# beginner.net
KiCad netlist of a schematic drawn in EAGLE
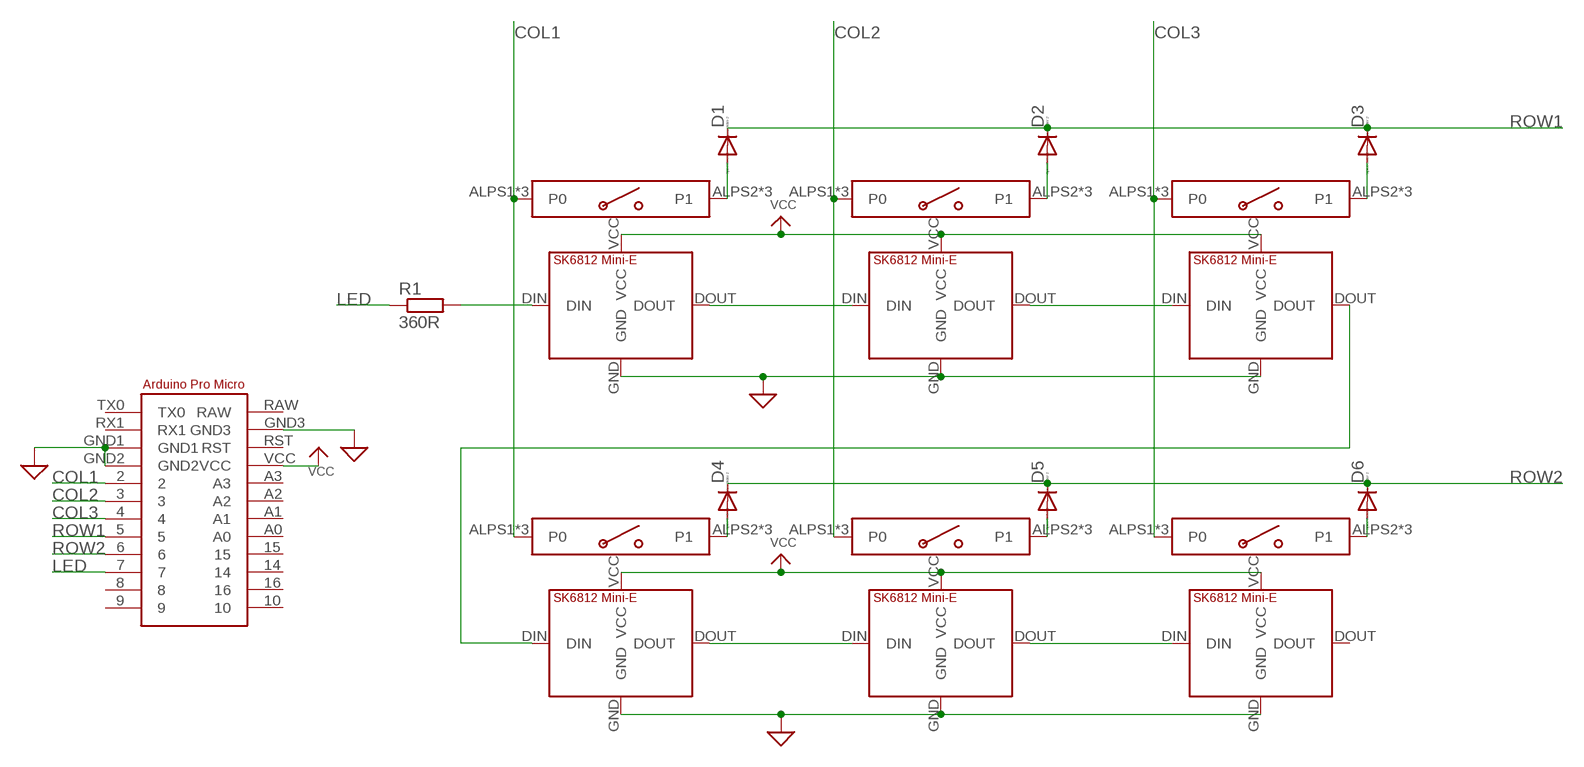
[diagram p0: schematic, sheet 1]

(export (version "E")
  (design (tool "Eeschema 10.0.6"))
  (components
    (comp (ref "D1")
      (value "1N41481N4148_THROUGH")
      (footprint "eagle-import:DIODE-1N4148")
      (libsource (lib "eagle-import") (part "1N41481N4148_THROUGH"))
    )
    (comp (ref "D2")
      (value "1N41481N4148_THROUGH")
      (footprint "eagle-import:DIODE-1N4148")
      (libsource (lib "eagle-import") (part "1N41481N4148_THROUGH"))
    )
    (comp (ref "D3")
      (value "1N41481N4148_THROUGH")
      (footprint "eagle-import:DIODE-1N4148")
      (libsource (lib "eagle-import") (part "1N41481N4148_THROUGH"))
    )
    (comp (ref "D4")
      (value "1N41481N4148_THROUGH")
      (footprint "eagle-import:DIODE-1N4148")
      (libsource (lib "eagle-import") (part "1N41481N4148_THROUGH"))
    )
    (comp (ref "D5")
      (value "1N41481N4148_THROUGH")
      (footprint "eagle-import:DIODE-1N4148")
      (libsource (lib "eagle-import") (part "1N41481N4148_THROUGH"))
    )
    (comp (ref "D6")
      (value "1N41481N4148_THROUGH")
      (footprint "eagle-import:DIODE-1N4148")
      (libsource (lib "eagle-import") (part "1N41481N4148_THROUGH"))
    )
    (comp (ref "R1")
      (value "360R")
      (footprint "eagle-import:THT-RESISTOR")
      (libsource (lib "eagle-import") (part "RESISTOR-THT"))
    )
    (comp (ref "U$1")
      (value "ARDUINO_PRO_MICRO")
      (footprint "eagle-import:ARDUINO_PRO_MICRO")
      (libsource (lib "eagle-import") (part "ARDUINO_PRO_MICRO"))
    )
    (comp (ref "U$2")
      (value "KEYSWITCH-SK6812")
      (footprint "eagle-import:UNIVERSAL_KEYSWITCH_SK6812MINIE")
      (libsource (lib "eagle-import") (part "KEYSWITCH-SK6812"))
    )
    (comp (ref "U$3")
      (value "KEYSWITCH-SK6812")
      (footprint "eagle-import:UNIVERSAL_KEYSWITCH_SK6812MINIE")
      (libsource (lib "eagle-import") (part "KEYSWITCH-SK6812"))
    )
    (comp (ref "U$4")
      (value "KEYSWITCH-SK6812")
      (footprint "eagle-import:UNIVERSAL_KEYSWITCH_SK6812MINIE")
      (libsource (lib "eagle-import") (part "KEYSWITCH-SK6812"))
    )
    (comp (ref "U$5")
      (value "KEYSWITCH-SK6812")
      (footprint "eagle-import:UNIVERSAL_KEYSWITCH_SK6812MINIE")
      (libsource (lib "eagle-import") (part "KEYSWITCH-SK6812"))
    )
    (comp (ref "U$6")
      (value "KEYSWITCH-SK6812")
      (footprint "eagle-import:UNIVERSAL_KEYSWITCH_SK6812MINIE")
      (libsource (lib "eagle-import") (part "KEYSWITCH-SK6812"))
    )
    (comp (ref "U$7")
      (value "KEYSWITCH-SK6812")
      (footprint "eagle-import:UNIVERSAL_KEYSWITCH_SK6812MINIE")
      (libsource (lib "eagle-import") (part "KEYSWITCH-SK6812"))
    )
  )
  (nets
    (net (code "1") (name "/COL1") (class "Default")
      (node (ref "U$1") (pin "2") (pinfunction "2_2") (pintype "bidirectional"))
      (node (ref "U$2") (pin "ALPS1") (pinfunction "P0_ALPS1") (pintype "bidirectional"))
      (node (ref "U$2") (pin "CHOC1") (pinfunction "P0_CHOC1") (pintype "bidirectional"))
      (node (ref "U$2") (pin "MX1") (pinfunction "P0_MX1") (pintype "bidirectional"))
      (node (ref "U$5") (pin "ALPS1") (pinfunction "P0_ALPS1") (pintype "bidirectional"))
      (node (ref "U$5") (pin "CHOC1") (pinfunction "P0_CHOC1") (pintype "bidirectional"))
      (node (ref "U$5") (pin "MX1") (pinfunction "P0_MX1") (pintype "bidirectional"))
    )
    (net (code "2") (name "/COL2") (class "Default")
      (node (ref "U$1") (pin "3") (pinfunction "3_3") (pintype "bidirectional"))
      (node (ref "U$3") (pin "ALPS1") (pinfunction "P0_ALPS1") (pintype "bidirectional"))
      (node (ref "U$3") (pin "CHOC1") (pinfunction "P0_CHOC1") (pintype "bidirectional"))
      (node (ref "U$3") (pin "MX1") (pinfunction "P0_MX1") (pintype "bidirectional"))
      (node (ref "U$6") (pin "ALPS1") (pinfunction "P0_ALPS1") (pintype "bidirectional"))
      (node (ref "U$6") (pin "CHOC1") (pinfunction "P0_CHOC1") (pintype "bidirectional"))
      (node (ref "U$6") (pin "MX1") (pinfunction "P0_MX1") (pintype "bidirectional"))
    )
    (net (code "3") (name "/COL3") (class "Default")
      (node (ref "U$1") (pin "4") (pinfunction "4_4") (pintype "bidirectional"))
      (node (ref "U$4") (pin "ALPS1") (pinfunction "P0_ALPS1") (pintype "bidirectional"))
      (node (ref "U$4") (pin "CHOC1") (pinfunction "P0_CHOC1") (pintype "bidirectional"))
      (node (ref "U$4") (pin "MX1") (pinfunction "P0_MX1") (pintype "bidirectional"))
      (node (ref "U$7") (pin "ALPS1") (pinfunction "P0_ALPS1") (pintype "bidirectional"))
      (node (ref "U$7") (pin "CHOC1") (pinfunction "P0_CHOC1") (pintype "bidirectional"))
      (node (ref "U$7") (pin "MX1") (pinfunction "P0_MX1") (pintype "bidirectional"))
    )
    (net (code "4") (name "/LED") (class "Default")
      (node (ref "R1") (pin "1") (pinfunction "1_1") (pintype "passive"))
      (node (ref "U$1") (pin "7") (pinfunction "7_7") (pintype "bidirectional"))
    )
    (net (code "5") (name "/ROW1") (class "Default")
      (node (ref "D1") (pin "C") (pinfunction "C_C") (pintype "passive"))
      (node (ref "D2") (pin "C") (pinfunction "C_C") (pintype "passive"))
      (node (ref "D3") (pin "C") (pinfunction "C_C") (pintype "passive"))
      (node (ref "U$1") (pin "5") (pinfunction "5_5") (pintype "bidirectional"))
    )
    (net (code "6") (name "/ROW2") (class "Default")
      (node (ref "D4") (pin "C") (pinfunction "C_C") (pintype "passive"))
      (node (ref "D5") (pin "C") (pinfunction "C_C") (pintype "passive"))
      (node (ref "D6") (pin "C") (pinfunction "C_C") (pintype "passive"))
      (node (ref "U$1") (pin "6") (pinfunction "6_6") (pintype "bidirectional"))
    )
    (net (code "7") (name "Net-(D1-PadA)") (class "Default")
      (node (ref "D1") (pin "A") (pinfunction "A_A") (pintype "passive"))
      (node (ref "U$2") (pin "ALPS2") (pinfunction "P1_ALPS2") (pintype "bidirectional"))
      (node (ref "U$2") (pin "CHOC2") (pinfunction "P1_CHOC2") (pintype "bidirectional"))
      (node (ref "U$2") (pin "MX2") (pinfunction "P1_MX2") (pintype "bidirectional"))
    )
    (net (code "8") (name "Net-(D2-PadA)") (class "Default")
      (node (ref "D2") (pin "A") (pinfunction "A_A") (pintype "passive"))
      (node (ref "U$3") (pin "ALPS2") (pinfunction "P1_ALPS2") (pintype "bidirectional"))
      (node (ref "U$3") (pin "CHOC2") (pinfunction "P1_CHOC2") (pintype "bidirectional"))
      (node (ref "U$3") (pin "MX2") (pinfunction "P1_MX2") (pintype "bidirectional"))
    )
    (net (code "9") (name "Net-(D3-PadA)") (class "Default")
      (node (ref "D3") (pin "A") (pinfunction "A_A") (pintype "passive"))
      (node (ref "U$4") (pin "ALPS2") (pinfunction "P1_ALPS2") (pintype "bidirectional"))
      (node (ref "U$4") (pin "CHOC2") (pinfunction "P1_CHOC2") (pintype "bidirectional"))
      (node (ref "U$4") (pin "MX2") (pinfunction "P1_MX2") (pintype "bidirectional"))
    )
    (net (code "10") (name "Net-(D4-PadA)") (class "Default")
      (node (ref "D4") (pin "A") (pinfunction "A_A") (pintype "passive"))
      (node (ref "U$5") (pin "ALPS2") (pinfunction "P1_ALPS2") (pintype "bidirectional"))
      (node (ref "U$5") (pin "CHOC2") (pinfunction "P1_CHOC2") (pintype "bidirectional"))
      (node (ref "U$5") (pin "MX2") (pinfunction "P1_MX2") (pintype "bidirectional"))
    )
    (net (code "11") (name "Net-(D5-PadA)") (class "Default")
      (node (ref "D5") (pin "A") (pinfunction "A_A") (pintype "passive"))
      (node (ref "U$6") (pin "ALPS2") (pinfunction "P1_ALPS2") (pintype "bidirectional"))
      (node (ref "U$6") (pin "CHOC2") (pinfunction "P1_CHOC2") (pintype "bidirectional"))
      (node (ref "U$6") (pin "MX2") (pinfunction "P1_MX2") (pintype "bidirectional"))
    )
    (net (code "12") (name "Net-(D6-PadA)") (class "Default")
      (node (ref "D6") (pin "A") (pinfunction "A_A") (pintype "passive"))
      (node (ref "U$7") (pin "ALPS2") (pinfunction "P1_ALPS2") (pintype "bidirectional"))
      (node (ref "U$7") (pin "CHOC2") (pinfunction "P1_CHOC2") (pintype "bidirectional"))
      (node (ref "U$7") (pin "MX2") (pinfunction "P1_MX2") (pintype "bidirectional"))
    )
    (net (code "13") (name "Net-(R1-Pad2)") (class "Default")
      (node (ref "R1") (pin "2") (pinfunction "2_2") (pintype "passive"))
      (node (ref "U$2") (pin "DIN") (pinfunction "DIN_DIN") (pintype "bidirectional"))
    )
    (net (code "14") (name "Net-(U$2-PadDOUT)") (class "Default")
      (node (ref "U$2") (pin "DOUT") (pinfunction "DOUT_DOUT") (pintype "bidirectional"))
      (node (ref "U$3") (pin "DIN") (pinfunction "DIN_DIN") (pintype "bidirectional"))
    )
    (net (code "15") (name "Net-(U$3-PadDOUT)") (class "Default")
      (node (ref "U$3") (pin "DOUT") (pinfunction "DOUT_DOUT") (pintype "bidirectional"))
      (node (ref "U$4") (pin "DIN") (pinfunction "DIN_DIN") (pintype "bidirectional"))
    )
    (net (code "16") (name "Net-(U$4-PadDOUT)") (class "Default")
      (node (ref "U$4") (pin "DOUT") (pinfunction "DOUT_DOUT") (pintype "bidirectional"))
      (node (ref "U$5") (pin "DIN") (pinfunction "DIN_DIN") (pintype "bidirectional"))
    )
    (net (code "17") (name "Net-(U$5-PadDOUT)") (class "Default")
      (node (ref "U$5") (pin "DOUT") (pinfunction "DOUT_DOUT") (pintype "bidirectional"))
      (node (ref "U$6") (pin "DIN") (pinfunction "DIN_DIN") (pintype "bidirectional"))
    )
    (net (code "18") (name "Net-(U$6-PadDOUT)") (class "Default")
      (node (ref "U$6") (pin "DOUT") (pinfunction "DOUT_DOUT") (pintype "bidirectional"))
      (node (ref "U$7") (pin "DIN") (pinfunction "DIN_DIN") (pintype "bidirectional"))
    )
    (net (code "19") (name "SUP") (class "Default")
      (node (ref "U$1") (pin "GND1") (pinfunction "GND1_GND1") (pintype "bidirectional"))
      (node (ref "U$1") (pin "GND2") (pinfunction "GND2_GND2") (pintype "bidirectional"))
      (node (ref "U$1") (pin "GND3") (pinfunction "GND3_GND3") (pintype "bidirectional"))
      (node (ref "U$2") (pin "GND") (pinfunction "GND_GND") (pintype "bidirectional"))
      (node (ref "U$3") (pin "GND") (pinfunction "GND_GND") (pintype "bidirectional"))
      (node (ref "U$4") (pin "GND") (pinfunction "GND_GND") (pintype "bidirectional"))
      (node (ref "U$5") (pin "GND") (pinfunction "GND_GND") (pintype "bidirectional"))
      (node (ref "U$6") (pin "GND") (pinfunction "GND_GND") (pintype "bidirectional"))
      (node (ref "U$7") (pin "GND") (pinfunction "GND_GND") (pintype "bidirectional"))
    )
    (net (code "20") (name "VCC") (class "Default")
      (node (ref "U$1") (pin "VCC") (pinfunction "VCC_VCC") (pintype "bidirectional"))
      (node (ref "U$2") (pin "VCC") (pinfunction "VCC_VCC") (pintype "bidirectional"))
      (node (ref "U$3") (pin "VCC") (pinfunction "VCC_VCC") (pintype "bidirectional"))
      (node (ref "U$4") (pin "VCC") (pinfunction "VCC_VCC") (pintype "bidirectional"))
      (node (ref "U$5") (pin "VCC") (pinfunction "VCC_VCC") (pintype "bidirectional"))
      (node (ref "U$6") (pin "VCC") (pinfunction "VCC_VCC") (pintype "bidirectional"))
      (node (ref "U$7") (pin "VCC") (pinfunction "VCC_VCC") (pintype "bidirectional"))
    )
    (net (code "21") (name "unconnected-(U$1-Pad8)") (class "Default")
      (node (ref "U$1") (pin "8") (pinfunction "8_8") (pintype "bidirectional"))
    )
    (net (code "22") (name "unconnected-(U$1-Pad9)") (class "Default")
      (node (ref "U$1") (pin "9") (pinfunction "9_9") (pintype "bidirectional"))
    )
    (net (code "23") (name "unconnected-(U$1-Pad10)") (class "Default")
      (node (ref "U$1") (pin "10") (pinfunction "10_10") (pintype "bidirectional"))
    )
    (net (code "24") (name "unconnected-(U$1-Pad14)") (class "Default")
      (node (ref "U$1") (pin "14") (pinfunction "14_14") (pintype "bidirectional"))
    )
    (net (code "25") (name "unconnected-(U$1-Pad15)") (class "Default")
      (node (ref "U$1") (pin "15") (pinfunction "15_15") (pintype "bidirectional"))
    )
    (net (code "26") (name "unconnected-(U$1-Pad16)") (class "Default")
      (node (ref "U$1") (pin "16") (pinfunction "16_16") (pintype "bidirectional"))
    )
    (net (code "27") (name "unconnected-(U$1-PadA0)") (class "Default")
      (node (ref "U$1") (pin "A0") (pinfunction "A0_A0") (pintype "bidirectional"))
    )
    (net (code "28") (name "unconnected-(U$1-PadA1)") (class "Default")
      (node (ref "U$1") (pin "A1") (pinfunction "A1_A1") (pintype "bidirectional"))
    )
    (net (code "29") (name "unconnected-(U$1-PadA2)") (class "Default")
      (node (ref "U$1") (pin "A2") (pinfunction "A2_A2") (pintype "bidirectional"))
    )
    (net (code "30") (name "unconnected-(U$1-PadA3)") (class "Default")
      (node (ref "U$1") (pin "A3") (pinfunction "A3_A3") (pintype "bidirectional"))
    )
    (net (code "31") (name "unconnected-(U$1-PadRAW)") (class "Default")
      (node (ref "U$1") (pin "RAW") (pinfunction "RAW_RAW") (pintype "bidirectional"))
    )
    (net (code "32") (name "unconnected-(U$1-PadRST)") (class "Default")
      (node (ref "U$1") (pin "RST") (pinfunction "RST_RST") (pintype "bidirectional"))
    )
    (net (code "33") (name "unconnected-(U$1-PadRX1)") (class "Default")
      (node (ref "U$1") (pin "RX1") (pinfunction "RX1_RX1") (pintype "bidirectional"))
    )
    (net (code "34") (name "unconnected-(U$1-PadTX0)") (class "Default")
      (node (ref "U$1") (pin "TX0") (pinfunction "TX0_TX0") (pintype "bidirectional"))
    )
    (net (code "35") (name "unconnected-(U$7-PadDOUT)") (class "Default")
      (node (ref "U$7") (pin "DOUT") (pinfunction "DOUT_DOUT") (pintype "bidirectional"))
    )
  )
)
